# LRTrobo.net
KiCad netlist of a schematic drawn in EAGLE
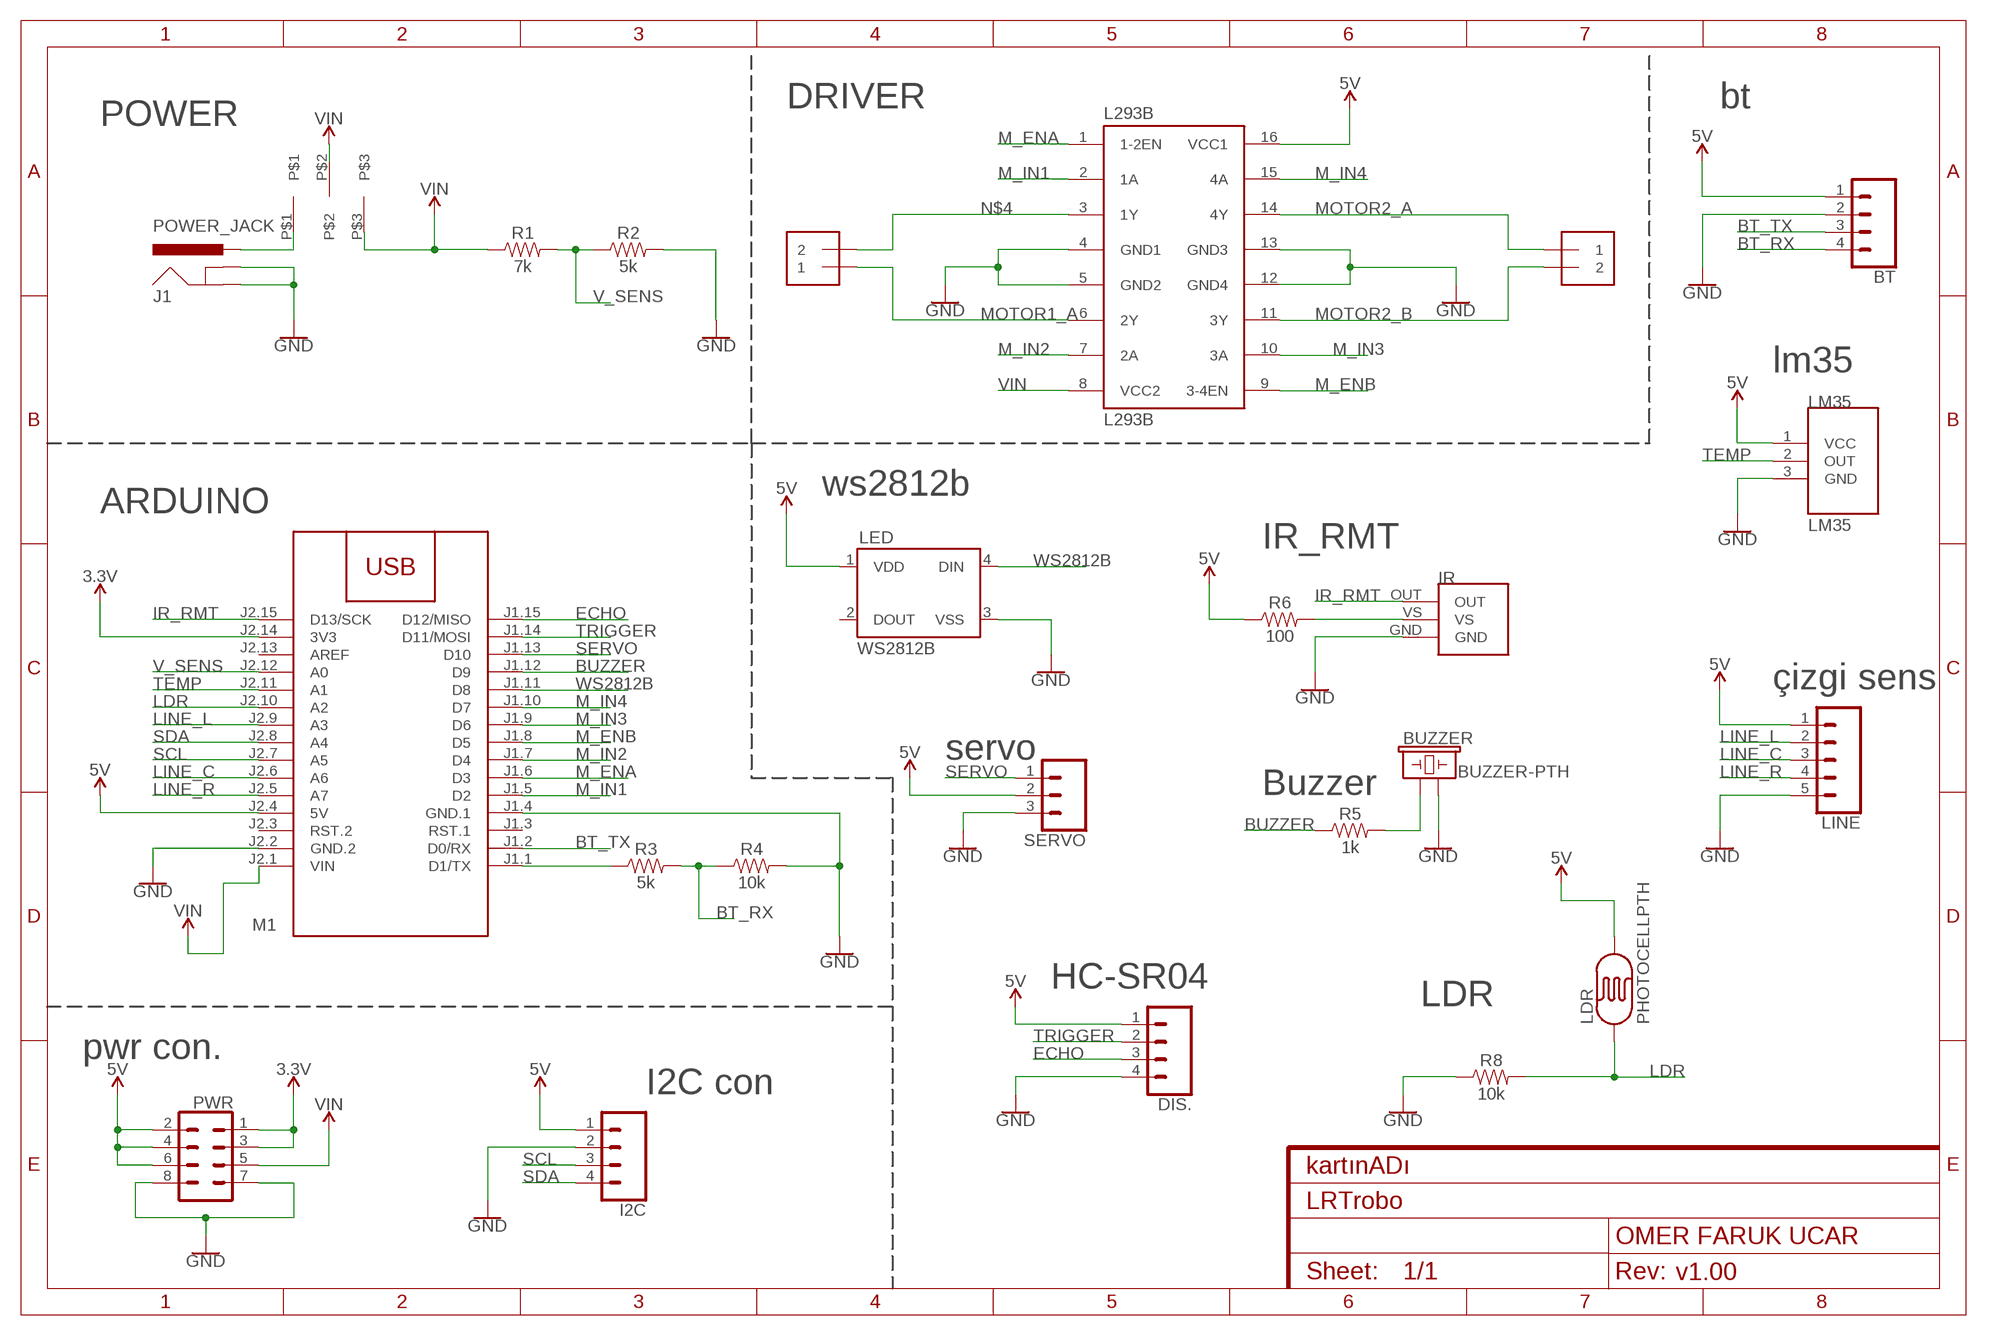
[diagram p0: schematic, sheet 1]

(export (version "E")
  (design (tool "Eeschema 10.0.6"))
  (components
    (comp (ref "BT")
      (value "CONN_04")
      (footprint "eagle-import:1X04")
      (libsource (lib "eagle-import") (part "CONN_04"))
    )
    (comp (ref "BUZZER")
      (value "BUZZER-PTH")
      (footprint "eagle-import:BUZZER-12MM")
      (libsource (lib "eagle-import") (part "BUZZER-PTH"))
    )
    (comp (ref "DIS.")
      (value "CONN_04")
      (footprint "eagle-import:1X04")
      (libsource (lib "eagle-import") (part "CONN_04"))
    )
    (comp (ref "I2C")
      (value "CONN_04")
      (footprint "eagle-import:1X04")
      (libsource (lib "eagle-import") (part "CONN_04"))
    )
    (comp (ref "IR")
      (value "TSOP2238THT")
      (footprint "eagle-import:TSOP2238")
      (libsource (lib "eagle-import") (part "TSOP2238THT"))
    )
    (comp (ref "J1")
      (value "POWER_JACK")
      (footprint "eagle-import:POWER_JACK_PTH")
      (libsource (lib "eagle-import") (part "POWER_JACK"))
    )
    (comp (ref "L293B")
      (value "L293B")
      (footprint "eagle-import:DIL16")
      (fields (field (name "MPN") "L293D"))
      (libsource (lib "eagle-import") (part "L293D"))
    )
    (comp (ref "LDR")
      (value "PHOTOCELLPTH")
      (footprint "eagle-import:PHOTOCELL")
      (libsource (lib "eagle-import") (part "PHOTOCELLPTH"))
    )
    (comp (ref "LED")
      (value "WS2812B")
      (footprint "eagle-import:WS2812B")
      (libsource (lib "eagle-import") (part "WS2812B"))
    )
    (comp (ref "LINE")
      (value "CONN_05")
      (footprint "eagle-import:1X05")
      (libsource (lib "eagle-import") (part "CONN_05"))
    )
    (comp (ref "LM35")
      (value "LM35")
      (footprint "eagle-import:TO-92")
      (libsource (lib "eagle-import") (part "LM35"))
    )
    (comp (ref "M1")
      (value "ARDUINO-NANO")
      (footprint "eagle-import:ARDUINO-NANO")
      (libsource (lib "eagle-import") (part "ARDUINO-NANO"))
    )
    (comp (ref "MPOWER")
      (value "1X2-3.5MM")
      (footprint "eagle-import:1X2-3.5MM")
      (libsource (lib "eagle-import") (part "1X2-3.5MM"))
    )
    (comp (ref "MPOWER1")
      (value "1X2-3.5MM")
      (footprint "eagle-import:1X2-3.5MM")
      (libsource (lib "eagle-import") (part "1X2-3.5MM"))
    )
    (comp (ref "PWR")
      (value "CONN_04X2")
      (footprint "eagle-import:2X4")
      (libsource (lib "eagle-import") (part "CONN_04X2"))
    )
    (comp (ref "R1")
      (value "7k")
      (footprint "eagle-import:AXIAL-0.3")
      (libsource (lib "eagle-import") (part "1KOHM-HORIZ-1/4W-5%"))
    )
    (comp (ref "R2")
      (value "5k")
      (footprint "eagle-import:AXIAL-0.3")
      (libsource (lib "eagle-import") (part "1KOHM-HORIZ-1/4W-5%"))
    )
    (comp (ref "R3")
      (value "5k")
      (footprint "eagle-import:AXIAL-0.3")
      (libsource (lib "eagle-import") (part "1KOHM-HORIZ-1/4W-5%"))
    )
    (comp (ref "R4")
      (value "10k")
      (footprint "eagle-import:AXIAL-0.3")
      (libsource (lib "eagle-import") (part "1KOHM-HORIZ-1/4W-5%"))
    )
    (comp (ref "R5")
      (value "1k")
      (footprint "eagle-import:AXIAL-0.3")
      (libsource (lib "eagle-import") (part "1KOHM-HORIZ-1/4W-5%"))
    )
    (comp (ref "R6")
      (value "100")
      (footprint "eagle-import:AXIAL-0.3")
      (libsource (lib "eagle-import") (part "1KOHM-HORIZ-1/4W-5%"))
    )
    (comp (ref "R8")
      (value "10k")
      (footprint "eagle-import:AXIAL-0.3")
      (libsource (lib "eagle-import") (part "1KOHM-HORIZ-1/4W-5%"))
    )
    (comp (ref "SERVO")
      (value "CONN_03")
      (footprint "eagle-import:1X03")
      (libsource (lib "eagle-import") (part "CONN_03"))
    )
    (comp (ref "SW1")
      (value "SW1")
      (footprint "eagle-import:SW1")
      (libsource (lib "eagle-import") (part "SW1"))
    )
  )
  (nets
    (net (code "1") (name "/BT_RX") (class "Default")
      (node (ref "BT") (pin "4") (pinfunction "4_4") (pintype "passive"))
      (node (ref "R3") (pin "P$2") (pinfunction "2_P$2") (pintype "passive"))
      (node (ref "R4") (pin "P$1") (pinfunction "1_P$1") (pintype "passive"))
    )
    (net (code "2") (name "/BT_TX") (class "Default")
      (node (ref "BT") (pin "3") (pinfunction "3_3") (pintype "passive"))
      (node (ref "M1") (pin "J1.2") (pinfunction "D0/RX_J1.2") (pintype "bidirectional"))
    )
    (net (code "3") (name "/BUZZER") (class "Default")
      (node (ref "M1") (pin "J1.12") (pinfunction "D9_J1.12") (pintype "bidirectional"))
      (node (ref "R5") (pin "P$1") (pinfunction "1_P$1") (pintype "passive"))
    )
    (net (code "4") (name "/ECHO") (class "Default")
      (node (ref "DIS.") (pin "3") (pinfunction "3_3") (pintype "passive"))
      (node (ref "M1") (pin "J1.15") (pinfunction "D12/MISO_J1.15") (pintype "bidirectional"))
    )
    (net (code "5") (name "/IR_RMT") (class "Default")
      (node (ref "IR") (pin "OUT") (pinfunction "OUT_OUT") (pintype "output"))
      (node (ref "M1") (pin "J2.15") (pinfunction "D13/SCK_J2.15") (pintype "bidirectional"))
    )
    (net (code "6") (name "/LDR") (class "Default")
      (node (ref "LDR") (pin "1") (pinfunction "P$1_1") (pintype "bidirectional"))
      (node (ref "M1") (pin "J2.10") (pinfunction "A2_J2.10") (pintype "bidirectional"))
      (node (ref "R8") (pin "P$2") (pinfunction "2_P$2") (pintype "passive"))
    )
    (net (code "7") (name "/LINE_C") (class "Default")
      (node (ref "LINE") (pin "3") (pinfunction "3_3") (pintype "passive"))
      (node (ref "M1") (pin "J2.6") (pinfunction "A6_J2.6") (pintype "bidirectional"))
    )
    (net (code "8") (name "/LINE_L") (class "Default")
      (node (ref "LINE") (pin "2") (pinfunction "2_2") (pintype "passive"))
      (node (ref "M1") (pin "J2.9") (pinfunction "A3_J2.9") (pintype "bidirectional"))
    )
    (net (code "9") (name "/LINE_R") (class "Default")
      (node (ref "LINE") (pin "4") (pinfunction "4_4") (pintype "passive"))
      (node (ref "M1") (pin "J2.5") (pinfunction "A7_J2.5") (pintype "bidirectional"))
    )
    (net (code "10") (name "/MOTOR1_A") (class "Default")
      (node (ref "L293B") (pin "6") (pinfunction "2Y_6") (pintype "output"))
      (node (ref "MPOWER") (pin "1") (pinfunction "1_1") (pintype "passive"))
    )
    (net (code "11") (name "/MOTOR2_A") (class "Default")
      (node (ref "L293B") (pin "14") (pinfunction "4Y_14") (pintype "output"))
      (node (ref "MPOWER1") (pin "1") (pinfunction "1_1") (pintype "passive"))
    )
    (net (code "12") (name "/MOTOR2_B") (class "Default")
      (node (ref "L293B") (pin "11") (pinfunction "3Y_11") (pintype "output"))
      (node (ref "MPOWER1") (pin "2") (pinfunction "2_2") (pintype "passive"))
    )
    (net (code "13") (name "/M_ENA") (class "Default")
      (node (ref "L293B") (pin "1") (pinfunction "1-2EN_1") (pintype "input"))
      (node (ref "M1") (pin "J1.6") (pinfunction "D3_J1.6") (pintype "bidirectional"))
    )
    (net (code "14") (name "/M_ENB") (class "Default")
      (node (ref "L293B") (pin "9") (pinfunction "3-4EN_9") (pintype "input"))
      (node (ref "M1") (pin "J1.8") (pinfunction "D5_J1.8") (pintype "bidirectional"))
    )
    (net (code "15") (name "/M_IN1") (class "Default")
      (node (ref "L293B") (pin "2") (pinfunction "1A_2") (pintype "input"))
      (node (ref "M1") (pin "J1.5") (pinfunction "D2_J1.5") (pintype "bidirectional"))
    )
    (net (code "16") (name "/M_IN2") (class "Default")
      (node (ref "L293B") (pin "7") (pinfunction "2A_7") (pintype "input"))
      (node (ref "M1") (pin "J1.7") (pinfunction "D4_J1.7") (pintype "bidirectional"))
    )
    (net (code "17") (name "/M_IN3") (class "Default")
      (node (ref "L293B") (pin "10") (pinfunction "3A_10") (pintype "input"))
      (node (ref "M1") (pin "J1.9") (pinfunction "D6_J1.9") (pintype "bidirectional"))
    )
    (net (code "18") (name "/M_IN4") (class "Default")
      (node (ref "L293B") (pin "15") (pinfunction "4A_15") (pintype "input"))
      (node (ref "M1") (pin "J1.10") (pinfunction "D7_J1.10") (pintype "bidirectional"))
    )
    (net (code "19") (name "/N$4") (class "Default")
      (node (ref "L293B") (pin "3") (pinfunction "1Y_3") (pintype "output"))
      (node (ref "MPOWER") (pin "2") (pinfunction "2_2") (pintype "passive"))
    )
    (net (code "20") (name "/SCL") (class "Default")
      (node (ref "I2C") (pin "3") (pinfunction "3_3") (pintype "passive"))
      (node (ref "M1") (pin "J2.7") (pinfunction "A5_J2.7") (pintype "bidirectional"))
    )
    (net (code "21") (name "/SDA") (class "Default")
      (node (ref "I2C") (pin "4") (pinfunction "4_4") (pintype "passive"))
      (node (ref "M1") (pin "J2.8") (pinfunction "A4_J2.8") (pintype "bidirectional"))
    )
    (net (code "22") (name "/SERVO") (class "Default")
      (node (ref "M1") (pin "J1.13") (pinfunction "D10_J1.13") (pintype "bidirectional"))
      (node (ref "SERVO") (pin "1") (pinfunction "1_1") (pintype "passive"))
    )
    (net (code "23") (name "/TEMP") (class "Default")
      (node (ref "LM35") (pin "2") (pinfunction "OUT_2") (pintype "bidirectional"))
      (node (ref "M1") (pin "J2.11") (pinfunction "A1_J2.11") (pintype "bidirectional"))
    )
    (net (code "24") (name "/TRIGGER") (class "Default")
      (node (ref "DIS.") (pin "2") (pinfunction "2_2") (pintype "passive"))
      (node (ref "M1") (pin "J1.14") (pinfunction "D11/MOSI_J1.14") (pintype "bidirectional"))
    )
    (net (code "25") (name "/V_SENS") (class "Default")
      (node (ref "M1") (pin "J2.12") (pinfunction "A0_J2.12") (pintype "bidirectional"))
      (node (ref "R1") (pin "P$2") (pinfunction "2_P$2") (pintype "passive"))
      (node (ref "R2") (pin "P$1") (pinfunction "1_P$1") (pintype "passive"))
    )
    (net (code "26") (name "/WS2812B") (class "Default")
      (node (ref "LED") (pin "4") (pinfunction "DIN_4") (pintype "input"))
      (node (ref "M1") (pin "J1.11") (pinfunction "D8_J1.11") (pintype "bidirectional"))
    )
    (net (code "27") (name "3.3V") (class "Default")
      (node (ref "M1") (pin "J2.14") (pinfunction "3V3_J2.14") (pintype "power_in"))
      (node (ref "PWR") (pin "1") (pinfunction "1_1") (pintype "passive"))
      (node (ref "PWR") (pin "3") (pinfunction "3_3") (pintype "passive"))
    )
    (net (code "28") (name "5V") (class "Default")
      (node (ref "BT") (pin "1") (pinfunction "1_1") (pintype "passive"))
      (node (ref "DIS.") (pin "1") (pinfunction "1_1") (pintype "passive"))
      (node (ref "I2C") (pin "1") (pinfunction "1_1") (pintype "passive"))
      (node (ref "L293B") (pin "16") (pinfunction "VCC1_16") (pintype "power_in"))
      (node (ref "LDR") (pin "2") (pinfunction "P$2_2") (pintype "bidirectional"))
      (node (ref "LED") (pin "1") (pinfunction "VDD_1") (pintype "power_in"))
      (node (ref "LINE") (pin "1") (pinfunction "1_1") (pintype "passive"))
      (node (ref "LM35") (pin "1") (pinfunction "VCC_1") (pintype "bidirectional"))
      (node (ref "M1") (pin "J2.4") (pinfunction "5V_J2.4") (pintype "power_in"))
      (node (ref "PWR") (pin "2") (pinfunction "2_2") (pintype "passive"))
      (node (ref "PWR") (pin "4") (pinfunction "4_4") (pintype "passive"))
      (node (ref "PWR") (pin "6") (pinfunction "6_6") (pintype "passive"))
      (node (ref "R6") (pin "P$1") (pinfunction "1_P$1") (pintype "passive"))
      (node (ref "SERVO") (pin "2") (pinfunction "2_2") (pintype "passive"))
    )
    (net (code "29") (name "GND") (class "Default")
      (node (ref "BT") (pin "2") (pinfunction "2_2") (pintype "passive"))
      (node (ref "BUZZER") (pin "-") (pinfunction "2_-") (pintype "passive"))
      (node (ref "DIS.") (pin "4") (pinfunction "4_4") (pintype "passive"))
      (node (ref "I2C") (pin "2") (pinfunction "2_2") (pintype "passive"))
      (node (ref "IR") (pin "GND") (pinfunction "GND_GND") (pintype "power_in"))
      (node (ref "J1") (pin "GND") (pinfunction "GND_GND") (pintype "bidirectional"))
      (node (ref "J1") (pin "GNDBREAK") (pinfunction "GNDBREAK_GNDBREAK") (pintype "bidirectional"))
      (node (ref "L293B") (pin "12") (pinfunction "GND4_12") (pintype "power_in"))
      (node (ref "L293B") (pin "13") (pinfunction "GND3_13") (pintype "power_in"))
      (node (ref "L293B") (pin "4") (pinfunction "GND1_4") (pintype "power_in"))
      (node (ref "L293B") (pin "5") (pinfunction "GND2_5") (pintype "power_in"))
      (node (ref "LED") (pin "3") (pinfunction "VSS_3") (pintype "power_in"))
      (node (ref "LINE") (pin "5") (pinfunction "5_5") (pintype "passive"))
      (node (ref "LM35") (pin "3") (pinfunction "GND_3") (pintype "bidirectional"))
      (node (ref "M1") (pin "J1.4") (pinfunction "GND.1_J1.4") (pintype "power_in"))
      (node (ref "M1") (pin "J2.2") (pinfunction "GND.2_J2.2") (pintype "power_in"))
      (node (ref "PWR") (pin "7") (pinfunction "7_7") (pintype "passive"))
      (node (ref "PWR") (pin "8") (pinfunction "8_8") (pintype "passive"))
      (node (ref "R2") (pin "P$2") (pinfunction "2_P$2") (pintype "passive"))
      (node (ref "R4") (pin "P$2") (pinfunction "2_P$2") (pintype "passive"))
      (node (ref "R8") (pin "P$1") (pinfunction "1_P$1") (pintype "passive"))
      (node (ref "SERVO") (pin "3") (pinfunction "3_3") (pintype "passive"))
    )
    (net (code "30") (name "Net-(BUZZER-1)") (class "Default")
      (node (ref "BUZZER") (pin "+") (pinfunction "1_+") (pintype "passive"))
      (node (ref "R5") (pin "P$2") (pinfunction "2_P$2") (pintype "passive"))
    )
    (net (code "31") (name "Net-(J1-PadPWR)") (class "Default")
      (node (ref "J1") (pin "PWR") (pinfunction "PWR_PWR") (pintype "bidirectional"))
      (node (ref "SW1") (pin "P$1") (pinfunction "P$1_P$1") (pintype "bidirectional"))
    )
    (net (code "32") (name "Net-(M1-D1{slash}TX)") (class "Default")
      (node (ref "M1") (pin "J1.1") (pinfunction "D1/TX_J1.1") (pintype "bidirectional"))
      (node (ref "R3") (pin "P$1") (pinfunction "1_P$1") (pintype "passive"))
    )
    (net (code "33") (name "Net-(R6-2)") (class "Default")
      (node (ref "IR") (pin "VS") (pinfunction "VS_VS") (pintype "power_in"))
      (node (ref "R6") (pin "P$2") (pinfunction "2_P$2") (pintype "passive"))
    )
    (net (code "34") (name "VIN") (class "Default")
      (node (ref "L293B") (pin "8") (pinfunction "VCC2_8") (pintype "power_in"))
      (node (ref "M1") (pin "J2.1") (pinfunction "VIN_J2.1") (pintype "power_in"))
      (node (ref "PWR") (pin "5") (pinfunction "5_5") (pintype "passive"))
      (node (ref "R1") (pin "P$1") (pinfunction "1_P$1") (pintype "passive"))
      (node (ref "SW1") (pin "P$2") (pinfunction "P$2_P$2") (pintype "bidirectional"))
      (node (ref "SW1") (pin "P$3") (pinfunction "P$3_P$3") (pintype "bidirectional"))
    )
    (net (code "35") (name "unconnected-(LED-DOUT-Pad2)") (class "Default")
      (node (ref "LED") (pin "2") (pinfunction "DOUT_2") (pintype "output"))
    )
    (net (code "36") (name "unconnected-(M1-AREF-PadJ2.13)") (class "Default")
      (node (ref "M1") (pin "J2.13") (pinfunction "AREF_J2.13") (pintype "bidirectional"))
    )
    (net (code "37") (name "unconnected-(M1-RST.1-PadJ1.3)") (class "Default")
      (node (ref "M1") (pin "J1.3") (pinfunction "RST.1_J1.3") (pintype "bidirectional"))
    )
    (net (code "38") (name "unconnected-(M1-RST.2-PadJ2.3)") (class "Default")
      (node (ref "M1") (pin "J2.3") (pinfunction "RST.2_J2.3") (pintype "bidirectional"))
    )
  )
)
